# Digipot.net
KiCad netlist of a schematic drawn in EAGLE
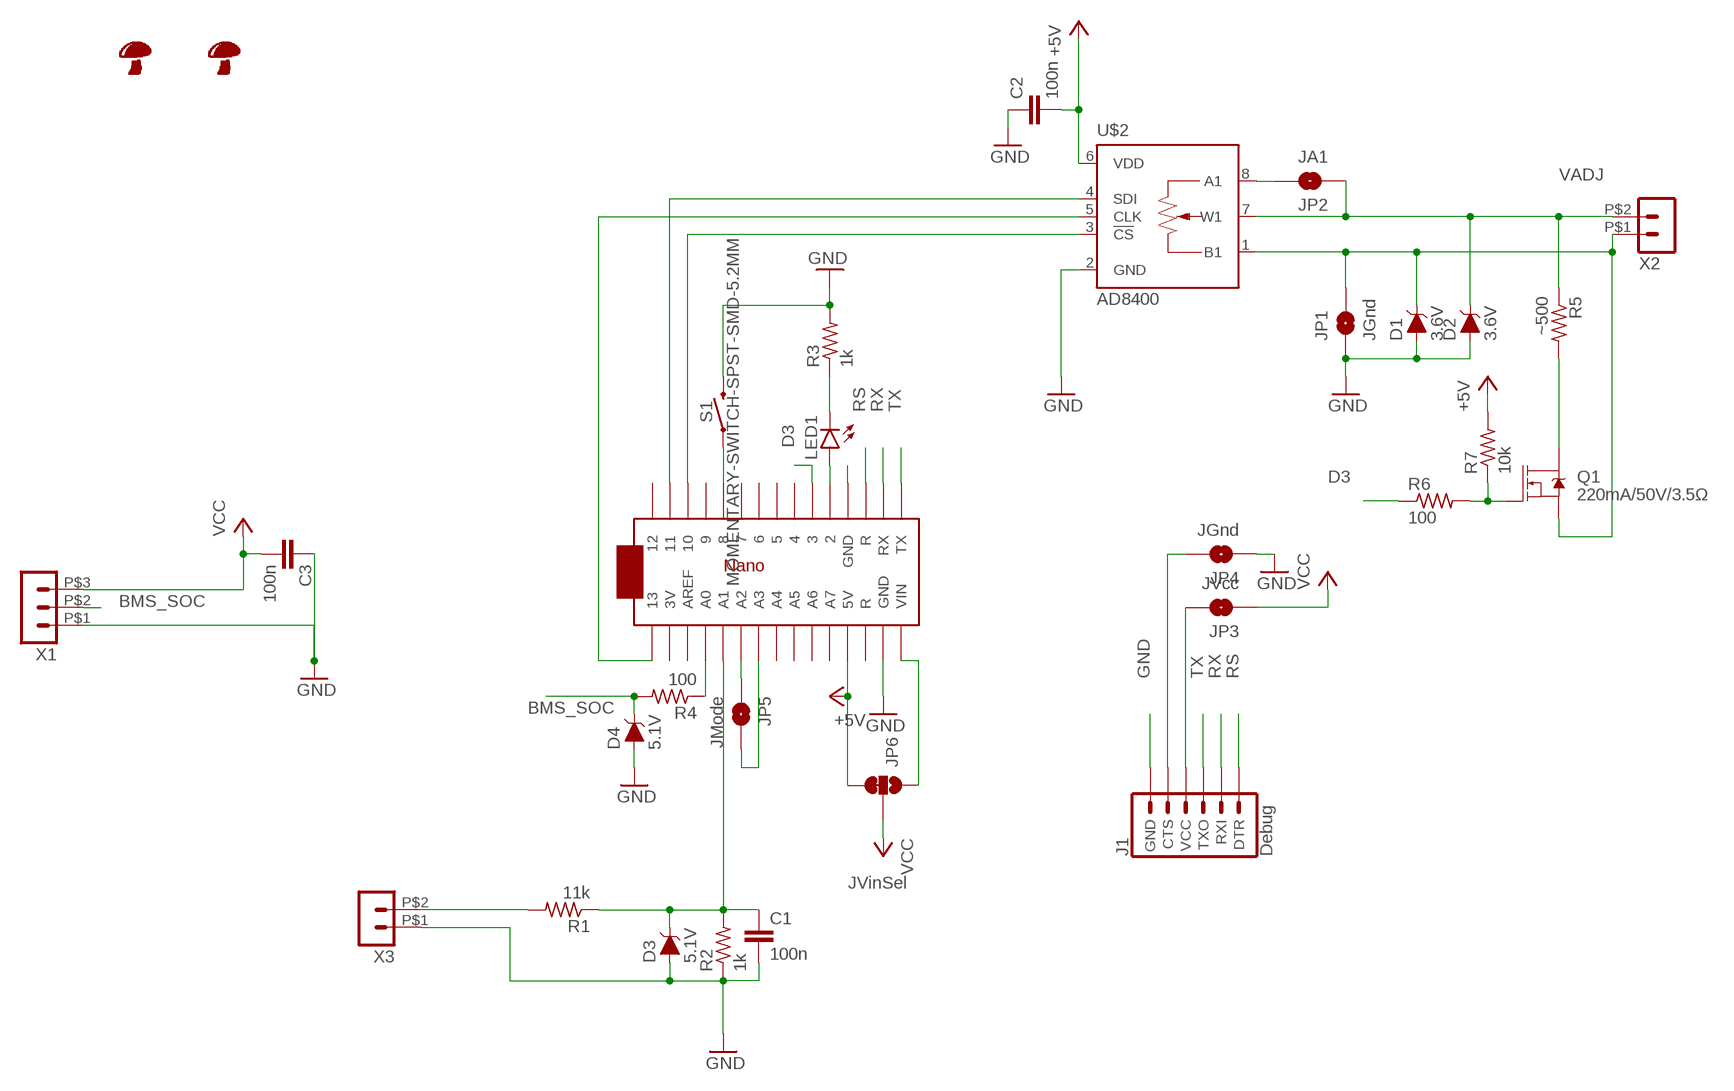
[diagram p0: schematic, sheet 1]

(export (version "E")
  (design (tool "Eeschema 10.0.6"))
  (components
    (comp (ref "C1")
      (value "100n")
      (footprint "eagle-import:C0805")
      (libsource (lib "eagle-import") (part "C-EUC0805"))
    )
    (comp (ref "C2")
      (value "100n")
      (footprint "eagle-import:C0805")
      (libsource (lib "eagle-import") (part "C-EUC0805"))
    )
    (comp (ref "C3")
      (value "100n")
      (footprint "eagle-import:C0805")
      (libsource (lib "eagle-import") (part "C-EUC0805"))
    )
    (comp (ref "D1")
      (value "3.6V")
      (footprint "eagle-import:SOD-323")
      (libsource (lib "eagle-import") (part "DIODE-ZENER-BZT52C3V6S"))
    )
    (comp (ref "D2")
      (value "3.6V")
      (footprint "eagle-import:SOD-323")
      (libsource (lib "eagle-import") (part "DIODE-ZENER-BZT52C3V6S"))
    )
    (comp (ref "D3")
      (value "5.1V")
      (footprint "eagle-import:SOD-323")
      (libsource (lib "eagle-import") (part "DIODE-ZENER-BZT52C3V6S"))
    )
    (comp (ref "D4")
      (value "5.1V")
      (footprint "eagle-import:SOD-323")
      (libsource (lib "eagle-import") (part "DIODE-ZENER-BZT52C3V6S"))
    )
    (comp (ref "J1")
      (value "Debug")
      (footprint "eagle-import:1X06_LOCK")
      (libsource (lib "eagle-import") (part "6_PIN_SERIAL_TARGETLOCK"))
    )
    (comp (ref "JP1")
      (value "JGnd")
      (footprint "eagle-import:SMT-JUMPER_2_NO_SILK")
      (libsource (lib "eagle-import") (part "JUMPER-SMT_2_NO_SILK"))
    )
    (comp (ref "JP2")
      (value "JA1")
      (footprint "eagle-import:SMT-JUMPER_2_NO_SILK")
      (libsource (lib "eagle-import") (part "JUMPER-SMT_2_NO_SILK"))
    )
    (comp (ref "JP3")
      (value "JVcc")
      (footprint "eagle-import:SMT-JUMPER_2_NO_SILK")
      (libsource (lib "eagle-import") (part "JUMPER-SMT_2_NO_SILK"))
    )
    (comp (ref "JP4")
      (value "JGnd")
      (footprint "eagle-import:SMT-JUMPER_2_NO_SILK")
      (libsource (lib "eagle-import") (part "JUMPER-SMT_2_NO_SILK"))
    )
    (comp (ref "JP5")
      (value "JMode")
      (footprint "eagle-import:SMT-JUMPER_2_NO_SILK")
      (libsource (lib "eagle-import") (part "JUMPER-SMT_2_NO_SILK"))
    )
    (comp (ref "JP6")
      (value "JVinSel")
      (footprint "eagle-import:SMT-JUMPER_3_1-NC_TRACE_SILK")
      (libsource (lib "eagle-import") (part "JUMPER-SMT_3_1-NC_TRACE_SILK"))
    )
    (comp (ref "LED1")
      (value "LEDCHIPLED_0805")
      (footprint "eagle-import:CHIPLED_0805")
      (libsource (lib "eagle-import") (part "LEDCHIPLED_0805"))
    )
    (comp (ref "Q1")
      (value "220mA/50V/3.5Ω")
      (footprint "eagle-import:SOT23-3")
      (libsource (lib "eagle-import") (part "MOSFET-NCH-BSS138"))
    )
    (comp (ref "R1")
      (value "11k")
      (footprint "eagle-import:R0805")
      (libsource (lib "eagle-import") (part "R-US_R0805"))
    )
    (comp (ref "R2")
      (value "1k")
      (footprint "eagle-import:R0805")
      (libsource (lib "eagle-import") (part "R-US_R0805"))
    )
    (comp (ref "R3")
      (value "1k")
      (footprint "eagle-import:R0805")
      (libsource (lib "eagle-import") (part "R-US_R0805"))
    )
    (comp (ref "R4")
      (value "100")
      (footprint "eagle-import:R0805")
      (libsource (lib "eagle-import") (part "R-US_R0805"))
    )
    (comp (ref "R5")
      (value "~500")
      (footprint "eagle-import:R0805")
      (libsource (lib "eagle-import") (part "R-US_R0805"))
    )
    (comp (ref "R6")
      (value "100")
      (footprint "eagle-import:R0805")
      (libsource (lib "eagle-import") (part "R-US_R0805"))
    )
    (comp (ref "R7")
      (value "10k")
      (footprint "eagle-import:R0805")
      (libsource (lib "eagle-import") (part "R-US_R0805"))
    )
    (comp (ref "S1")
      (value "MOMENTARY-SWITCH-SPST-SMD-5.2MM")
      (footprint "eagle-import:TACTILE_SWITCH_SMD_5.2MM")
      (libsource (lib "eagle-import") (part "MOMENTARY-SWITCH-SPST-SMD-5.2MM"))
    )
    (comp (ref "U$1")
      (value "ARDUINO_NANOARDUINONANO")
      (footprint "eagle-import:ARDUINOMICRO")
      (libsource (lib "eagle-import") (part "ARDUINO_NANOARDUINONANO"))
    )
    (comp (ref "U$2")
      (value "AD8400")
      (footprint "eagle-import:SOIC08")
      (libsource (lib "eagle-import") (part "AD8400"))
    )
    (comp (ref "U$3")
      (value "SHROOMTOPSILK")
      (footprint "eagle-import:SHROOM_TS")
      (libsource (lib "eagle-import") (part "SHROOMTOPSILK"))
    )
    (comp (ref "U$4")
      (value "SHROOM5MM")
      (footprint "eagle-import:SHROOM")
      (libsource (lib "eagle-import") (part "SHROOM5MM"))
    )
    (comp (ref "X1")
      (value "HEADER_POS3_43650-0300")
      (footprint "eagle-import:43650-0300")
      (libsource (lib "eagle-import") (part "HEADER_POS3_?43650-0300"))
    )
    (comp (ref "X2")
      (value "HEADER_POS2_43650-0200")
      (footprint "eagle-import:43650-0200")
      (libsource (lib "eagle-import") (part "HEADER_POS2_?43650-0200"))
    )
    (comp (ref "X3")
      (value "HEADER_POS2_43650-0200")
      (footprint "eagle-import:43650-0200")
      (libsource (lib "eagle-import") (part "HEADER_POS2_?43650-0200"))
    )
  )
  (nets
    (net (code "1") (name "+5V") (class "Default")
      (node (ref "C2") (pin "2") (pinfunction "2_2") (pintype "passive"))
      (node (ref "JP6") (pin "3") (pinfunction "3_3") (pintype "passive"))
      (node (ref "R7") (pin "2") (pinfunction "2_2") (pintype "passive"))
      (node (ref "U$1") (pin "P$23") (pinfunction "5V_P$23") (pintype "bidirectional"))
      (node (ref "U$2") (pin "6") (pinfunction "VDD_6") (pintype "power_in"))
    )
    (net (code "2") (name "/BMS_SOC") (class "Default")
      (node (ref "D4") (pin "C") (pinfunction "C_C") (pintype "passive"))
      (node (ref "R4") (pin "2") (pinfunction "2_2") (pintype "passive"))
      (node (ref "X1") (pin "P$2") (pinfunction "2_P$2") (pintype "passive"))
    )
    (net (code "3") (name "/D3") (class "Default")
      (node (ref "R6") (pin "1") (pinfunction "1_1") (pintype "passive"))
      (node (ref "U$1") (pin "P$10") (pinfunction "3_P$10") (pintype "bidirectional"))
    )
    (net (code "4") (name "/RS") (class "Default")
      (node (ref "J1") (pin "1") (pinfunction "DTR_1") (pintype "passive"))
      (node (ref "U$1") (pin "P$22") (pinfunction "R_P$22") (pintype "bidirectional"))
    )
    (net (code "5") (name "/RX") (class "Default")
      (node (ref "J1") (pin "2") (pinfunction "RXI_2") (pintype "passive"))
      (node (ref "U$1") (pin "P$14") (pinfunction "RX_P$14") (pintype "bidirectional"))
    )
    (net (code "6") (name "/TX") (class "Default")
      (node (ref "J1") (pin "3") (pinfunction "TXO_3") (pintype "passive"))
      (node (ref "U$1") (pin "P$15") (pinfunction "TX_P$15") (pintype "bidirectional"))
    )
    (net (code "7") (name "/VADJ") (class "Default")
      (node (ref "D2") (pin "C") (pinfunction "C_C") (pintype "passive"))
      (node (ref "JP2") (pin "1") (pinfunction "1_1") (pintype "passive"))
      (node (ref "R5") (pin "1") (pinfunction "1_1") (pintype "passive"))
      (node (ref "U$2") (pin "7") (pinfunction "W1_7") (pintype "passive"))
      (node (ref "X2") (pin "P$2") (pinfunction "2_P$2") (pintype "passive"))
    )
    (net (code "8") (name "GND") (class "Default")
      (node (ref "C1") (pin "2") (pinfunction "2_2") (pintype "passive"))
      (node (ref "C2") (pin "1") (pinfunction "1_1") (pintype "passive"))
      (node (ref "C3") (pin "1") (pinfunction "1_1") (pintype "passive"))
      (node (ref "D1") (pin "A") (pinfunction "A_A") (pintype "passive"))
      (node (ref "D2") (pin "A") (pinfunction "A_A") (pintype "passive"))
      (node (ref "D3") (pin "A") (pinfunction "A_A") (pintype "passive"))
      (node (ref "D4") (pin "A") (pinfunction "A_A") (pintype "passive"))
      (node (ref "J1") (pin "6") (pinfunction "GND_6") (pintype "passive"))
      (node (ref "JP1") (pin "1") (pinfunction "1_1") (pintype "passive"))
      (node (ref "JP4") (pin "1") (pinfunction "1_1") (pintype "passive"))
      (node (ref "R2") (pin "1") (pinfunction "1_1") (pintype "passive"))
      (node (ref "R3") (pin "2") (pinfunction "2_2") (pintype "passive"))
      (node (ref "S1") (pin "3") (pinfunction "2_3") (pintype "passive"))
      (node (ref "U$1") (pin "P$12") (pinfunction "GND_P$12") (pintype "bidirectional"))
      (node (ref "U$1") (pin "P$21") (pinfunction "GND_P$21") (pintype "bidirectional"))
      (node (ref "U$2") (pin "2") (pinfunction "GND_2") (pintype "power_in"))
      (node (ref "X1") (pin "P$1") (pinfunction "1_P$1") (pintype "passive"))
      (node (ref "X3") (pin "P$1") (pinfunction "1_P$1") (pintype "passive"))
    )
    (net (code "9") (name "Net-(J1-CTS)") (class "Default")
      (node (ref "J1") (pin "5") (pinfunction "CTS_5") (pintype "passive"))
      (node (ref "JP4") (pin "2") (pinfunction "2_2") (pintype "passive"))
    )
    (net (code "10") (name "Net-(J1-VCC)") (class "Default")
      (node (ref "J1") (pin "4") (pinfunction "VCC_4") (pintype "passive"))
      (node (ref "JP3") (pin "2") (pinfunction "2_2") (pintype "passive"))
    )
    (net (code "11") (name "Net-(LED1-PadC)") (class "Default")
      (node (ref "LED1") (pin "C") (pinfunction "C_C") (pintype "passive"))
      (node (ref "R3") (pin "1") (pinfunction "1_1") (pintype "passive"))
    )
    (net (code "12") (name "Net-(Q1-D)") (class "Default")
      (node (ref "Q1") (pin "3") (pinfunction "D_3") (pintype "bidirectional"))
      (node (ref "R5") (pin "2") (pinfunction "2_2") (pintype "passive"))
    )
    (net (code "13") (name "Net-(Q1-G)") (class "Default")
      (node (ref "Q1") (pin "1") (pinfunction "G_1") (pintype "bidirectional"))
      (node (ref "R6") (pin "2") (pinfunction "2_2") (pintype "passive"))
      (node (ref "R7") (pin "1") (pinfunction "1_1") (pintype "passive"))
    )
    (net (code "14") (name "Net-(Q1-S)") (class "Default")
      (node (ref "D1") (pin "C") (pinfunction "C_C") (pintype "passive"))
      (node (ref "JP1") (pin "2") (pinfunction "2_2") (pintype "passive"))
      (node (ref "Q1") (pin "2") (pinfunction "S_2") (pintype "bidirectional"))
      (node (ref "U$2") (pin "1") (pinfunction "B1_1") (pintype "passive"))
      (node (ref "X2") (pin "P$1") (pinfunction "1_P$1") (pintype "passive"))
    )
    (net (code "15") (name "Net-(U$1-2)") (class "Default")
      (node (ref "LED1") (pin "A") (pinfunction "A_A") (pintype "passive"))
      (node (ref "U$1") (pin "P$11") (pinfunction "2_P$11") (pintype "bidirectional"))
    )
    (net (code "16") (name "Net-(U$1-8)") (class "Default")
      (node (ref "S1") (pin "1") (pinfunction "1_1") (pintype "passive"))
      (node (ref "U$1") (pin "P$5") (pinfunction "8_P$5") (pintype "bidirectional"))
    )
    (net (code "17") (name "Net-(U$1-10)") (class "Default")
      (node (ref "U$1") (pin "P$3") (pinfunction "10_P$3") (pintype "bidirectional"))
      (node (ref "U$2") (pin "3") (pinfunction "~{CS}_3") (pintype "input"))
    )
    (net (code "18") (name "Net-(U$1-11)") (class "Default")
      (node (ref "U$1") (pin "P$2") (pinfunction "11_P$2") (pintype "bidirectional"))
      (node (ref "U$2") (pin "4") (pinfunction "SDI_4") (pintype "input"))
    )
    (net (code "19") (name "Net-(U$1-13)") (class "Default")
      (node (ref "U$1") (pin "P$34") (pinfunction "13_P$34") (pintype "bidirectional"))
      (node (ref "U$2") (pin "5") (pinfunction "CLK_5") (pintype "input"))
    )
    (net (code "20") (name "Net-(U$1-A0)") (class "Default")
      (node (ref "R4") (pin "1") (pinfunction "1_1") (pintype "passive"))
      (node (ref "U$1") (pin "P$31") (pinfunction "A0_P$31") (pintype "bidirectional"))
    )
    (net (code "21") (name "Net-(U$1-A1)") (class "Default")
      (node (ref "C1") (pin "1") (pinfunction "1_1") (pintype "passive"))
      (node (ref "D3") (pin "C") (pinfunction "C_C") (pintype "passive"))
      (node (ref "R1") (pin "1") (pinfunction "1_1") (pintype "passive"))
      (node (ref "R2") (pin "2") (pinfunction "2_2") (pintype "passive"))
      (node (ref "U$1") (pin "P$30") (pinfunction "A1_P$30") (pintype "bidirectional"))
    )
    (net (code "22") (name "Net-(U$1-A2)") (class "Default")
      (node (ref "JP5") (pin "1") (pinfunction "1_1") (pintype "passive"))
      (node (ref "U$1") (pin "P$29") (pinfunction "A2_P$29") (pintype "bidirectional"))
    )
    (net (code "23") (name "Net-(U$1-A3)") (class "Default")
      (node (ref "JP5") (pin "2") (pinfunction "2_2") (pintype "passive"))
      (node (ref "U$1") (pin "P$28") (pinfunction "A3_P$28") (pintype "bidirectional"))
    )
    (net (code "24") (name "Net-(U$1-VIN)") (class "Default")
      (node (ref "JP6") (pin "1") (pinfunction "1_1") (pintype "passive"))
      (node (ref "U$1") (pin "P$20") (pinfunction "VIN_P$20") (pintype "bidirectional"))
    )
    (net (code "25") (name "Net-(U$2-A1)") (class "Default")
      (node (ref "JP2") (pin "2") (pinfunction "2_2") (pintype "passive"))
      (node (ref "U$2") (pin "8") (pinfunction "A1_8") (pintype "passive"))
    )
    (net (code "26") (name "Net-(X3-2)") (class "Default")
      (node (ref "R1") (pin "2") (pinfunction "2_2") (pintype "passive"))
      (node (ref "X3") (pin "P$2") (pinfunction "2_P$2") (pintype "passive"))
    )
    (net (code "27") (name "VCC") (class "Default")
      (node (ref "C3") (pin "2") (pinfunction "2_2") (pintype "passive"))
      (node (ref "JP3") (pin "1") (pinfunction "1_1") (pintype "passive"))
      (node (ref "JP6") (pin "2") (pinfunction "2_2") (pintype "passive"))
      (node (ref "X1") (pin "P$3") (pinfunction "3_P$3") (pintype "passive"))
    )
    (net (code "28") (name "unconnected-(U$1-3V-PadP$33)") (class "Default")
      (node (ref "U$1") (pin "P$33") (pinfunction "3V_P$33") (pintype "bidirectional"))
    )
    (net (code "29") (name "unconnected-(U$1-4-PadP$9)") (class "Default")
      (node (ref "U$1") (pin "P$9") (pinfunction "4_P$9") (pintype "bidirectional"))
    )
    (net (code "30") (name "unconnected-(U$1-5-PadP$8)") (class "Default")
      (node (ref "U$1") (pin "P$8") (pinfunction "5_P$8") (pintype "bidirectional"))
    )
    (net (code "31") (name "unconnected-(U$1-6-PadP$7)") (class "Default")
      (node (ref "U$1") (pin "P$7") (pinfunction "6_P$7") (pintype "bidirectional"))
    )
    (net (code "32") (name "unconnected-(U$1-7-PadP$6)") (class "Default")
      (node (ref "U$1") (pin "P$6") (pinfunction "7_P$6") (pintype "bidirectional"))
    )
    (net (code "33") (name "unconnected-(U$1-9-PadP$4)") (class "Default")
      (node (ref "U$1") (pin "P$4") (pinfunction "9_P$4") (pintype "bidirectional"))
    )
    (net (code "34") (name "unconnected-(U$1-12-PadP$1)") (class "Default")
      (node (ref "U$1") (pin "P$1") (pinfunction "12_P$1") (pintype "bidirectional"))
    )
    (net (code "35") (name "unconnected-(U$1-A4-PadP$27)") (class "Default")
      (node (ref "U$1") (pin "P$27") (pinfunction "A4_P$27") (pintype "bidirectional"))
    )
    (net (code "36") (name "unconnected-(U$1-A5-PadP$26)") (class "Default")
      (node (ref "U$1") (pin "P$26") (pinfunction "A5_P$26") (pintype "bidirectional"))
    )
    (net (code "37") (name "unconnected-(U$1-A6-PadP$25)") (class "Default")
      (node (ref "U$1") (pin "P$25") (pinfunction "A6_P$25") (pintype "bidirectional"))
    )
    (net (code "38") (name "unconnected-(U$1-A7-PadP$24)") (class "Default")
      (node (ref "U$1") (pin "P$24") (pinfunction "A7_P$24") (pintype "bidirectional"))
    )
    (net (code "39") (name "unconnected-(U$1-AREF-PadP$32)") (class "Default")
      (node (ref "U$1") (pin "P$32") (pinfunction "AREF_P$32") (pintype "bidirectional"))
    )
    (net (code "40") (name "unconnected-(U$1-R-PadP$13)") (class "Default")
      (node (ref "U$1") (pin "P$13") (pinfunction "R_P$13") (pintype "bidirectional"))
    )
  )
)
